# Hammerhead_-_MAX11300_Analog_Hub_R1_1.net
KiCad netlist of a schematic drawn in Altium Designer
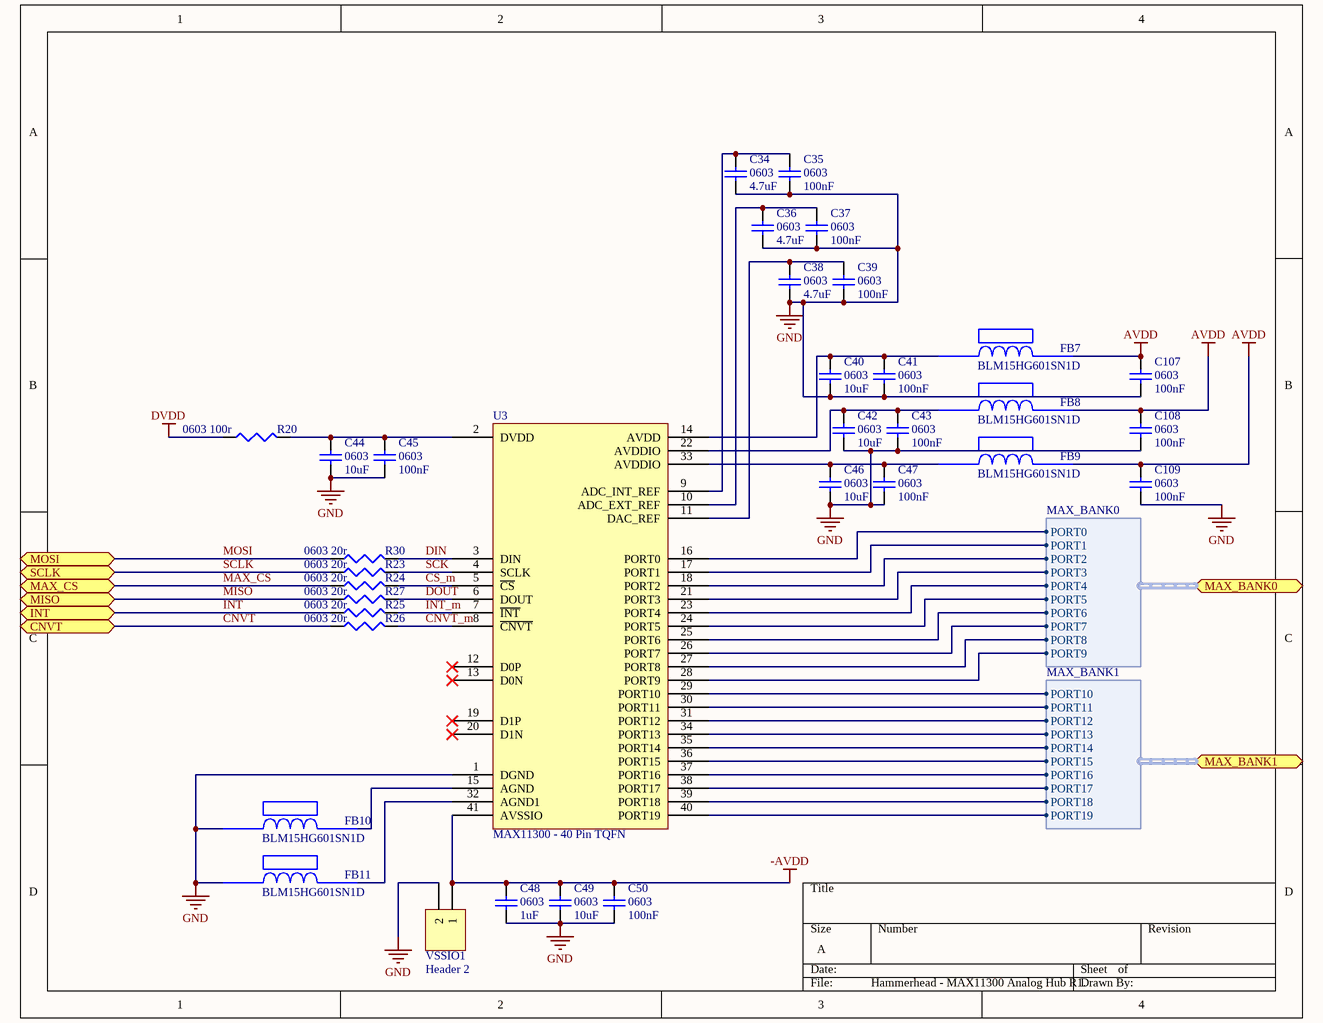
[diagram p0: Hammerhead - MAX11300 Analog Hub R1.1.SchDoc]

(export (version "E")
  (design (tool "Eeschema 10.0.6"))
  (components
    (comp (ref "C34")
      (value "0603")
      (footprint "1608[0603]")
      (description "Capacitor (Semiconductor SIM Model)")
      (fields (field (name "ALTIUM_VALUE") "4.7uF") (field (name "PUBLISHER") "Altium Limited"))
      (libsource (lib "Miscellaneous Devices") (part "Cap Semi"))
    )
    (comp (ref "C35")
      (value "0603")
      (footprint "1608[0603]")
      (description "Capacitor (Semiconductor SIM Model)")
      (fields (field (name "ALTIUM_VALUE") "100nF") (field (name "PUBLISHER") "Altium Limited"))
      (libsource (lib "Miscellaneous Devices") (part "Cap Semi"))
    )
    (comp (ref "C36")
      (value "0603")
      (footprint "1608[0603]")
      (description "Capacitor (Semiconductor SIM Model)")
      (fields (field (name "ALTIUM_VALUE") "4.7uF") (field (name "PUBLISHER") "Altium Limited"))
      (libsource (lib "Miscellaneous Devices") (part "Cap Semi"))
    )
    (comp (ref "C37")
      (value "0603")
      (footprint "1608[0603]")
      (description "Capacitor (Semiconductor SIM Model)")
      (fields (field (name "ALTIUM_VALUE") "100nF") (field (name "PUBLISHER") "Altium Limited"))
      (libsource (lib "Miscellaneous Devices") (part "Cap Semi"))
    )
    (comp (ref "C38")
      (value "0603")
      (footprint "1608[0603]")
      (description "Capacitor (Semiconductor SIM Model)")
      (fields (field (name "ALTIUM_VALUE") "4.7uF") (field (name "PUBLISHER") "Altium Limited"))
      (libsource (lib "Miscellaneous Devices") (part "Cap Semi"))
    )
    (comp (ref "C39")
      (value "0603")
      (footprint "1608[0603]")
      (description "Capacitor (Semiconductor SIM Model)")
      (fields (field (name "ALTIUM_VALUE") "100nF") (field (name "PUBLISHER") "Altium Limited"))
      (libsource (lib "Miscellaneous Devices") (part "Cap Semi"))
    )
    (comp (ref "C40")
      (value "0603")
      (footprint "1608[0603]")
      (description "Capacitor (Semiconductor SIM Model)")
      (fields (field (name "ALTIUM_VALUE") "10uF") (field (name "PUBLISHER") "Altium Limited"))
      (libsource (lib "Miscellaneous Devices") (part "Cap Semi"))
    )
    (comp (ref "C41")
      (value "0603")
      (footprint "1608[0603]")
      (description "Capacitor (Semiconductor SIM Model)")
      (fields (field (name "ALTIUM_VALUE") "100nF") (field (name "PUBLISHER") "Altium Limited"))
      (libsource (lib "Miscellaneous Devices") (part "Cap Semi"))
    )
    (comp (ref "C42")
      (value "0603")
      (footprint "1608[0603]")
      (description "Capacitor (Semiconductor SIM Model)")
      (fields (field (name "ALTIUM_VALUE") "10uF") (field (name "PUBLISHER") "Altium Limited"))
      (libsource (lib "Miscellaneous Devices") (part "Cap Semi"))
    )
    (comp (ref "C43")
      (value "0603")
      (footprint "1608[0603]")
      (description "Capacitor (Semiconductor SIM Model)")
      (fields (field (name "ALTIUM_VALUE") "100nF") (field (name "PUBLISHER") "Altium Limited"))
      (libsource (lib "Miscellaneous Devices") (part "Cap Semi"))
    )
    (comp (ref "C44")
      (value "0603")
      (footprint "1608[0603]")
      (description "Capacitor (Semiconductor SIM Model)")
      (fields (field (name "ALTIUM_VALUE") "10uF") (field (name "PUBLISHER") "Altium Limited"))
      (libsource (lib "Miscellaneous Devices") (part "Cap Semi"))
    )
    (comp (ref "C45")
      (value "0603")
      (footprint "1608[0603]")
      (description "Capacitor (Semiconductor SIM Model)")
      (fields (field (name "ALTIUM_VALUE") "100nF") (field (name "PUBLISHER") "Altium Limited"))
      (libsource (lib "Miscellaneous Devices") (part "Cap Semi"))
    )
    (comp (ref "C46")
      (value "0603")
      (footprint "1608[0603]")
      (description "Capacitor (Semiconductor SIM Model)")
      (fields (field (name "ALTIUM_VALUE") "10uF") (field (name "PUBLISHER") "Altium Limited"))
      (libsource (lib "Miscellaneous Devices") (part "Cap Semi"))
    )
    (comp (ref "C47")
      (value "0603")
      (footprint "1608[0603]")
      (description "Capacitor (Semiconductor SIM Model)")
      (fields (field (name "ALTIUM_VALUE") "100nF") (field (name "PUBLISHER") "Altium Limited"))
      (libsource (lib "Miscellaneous Devices") (part "Cap Semi"))
    )
    (comp (ref "C48")
      (value "0603")
      (footprint "1608[0603]")
      (description "Capacitor (Semiconductor SIM Model)")
      (fields (field (name "ALTIUM_VALUE") "1uF") (field (name "PUBLISHER") "Altium Limited"))
      (libsource (lib "Miscellaneous Devices") (part "Cap Semi"))
    )
    (comp (ref "C49")
      (value "0603")
      (footprint "1608[0603]")
      (description "Capacitor (Semiconductor SIM Model)")
      (fields (field (name "ALTIUM_VALUE") "10uF") (field (name "PUBLISHER") "Altium Limited"))
      (libsource (lib "Miscellaneous Devices") (part "Cap Semi"))
    )
    (comp (ref "C50")
      (value "0603")
      (footprint "1608[0603]")
      (description "Capacitor (Semiconductor SIM Model)")
      (fields (field (name "ALTIUM_VALUE") "100nF") (field (name "PUBLISHER") "Altium Limited"))
      (libsource (lib "Miscellaneous Devices") (part "Cap Semi"))
    )
    (comp (ref "C107")
      (value "0603")
      (footprint "1608[0603]")
      (description "Capacitor (Semiconductor SIM Model)")
      (fields (field (name "ALTIUM_VALUE") "100nF") (field (name "PUBLISHER") "Altium Limited"))
      (libsource (lib "Miscellaneous Devices") (part "Cap Semi"))
    )
    (comp (ref "C108")
      (value "0603")
      (footprint "1608[0603]")
      (description "Capacitor (Semiconductor SIM Model)")
      (fields (field (name "ALTIUM_VALUE") "100nF") (field (name "PUBLISHER") "Altium Limited"))
      (libsource (lib "Miscellaneous Devices") (part "Cap Semi"))
    )
    (comp (ref "C109")
      (value "0603")
      (footprint "1608[0603]")
      (description "Capacitor (Semiconductor SIM Model)")
      (fields (field (name "ALTIUM_VALUE") "100nF") (field (name "PUBLISHER") "Altium Limited"))
      (libsource (lib "Miscellaneous Devices") (part "Cap Semi"))
    )
    (comp (ref "FB7")
      (value "BLM15HG601SN1D")
      (footprint "BLM18PG121SN1D")
      (libsource (lib "AHD Part Library") (part "BLM15HG601SN1D"))
    )
    (comp (ref "FB8")
      (value "BLM15HG601SN1D")
      (footprint "BLM18PG121SN1D")
      (libsource (lib "AHD Part Library") (part "BLM15HG601SN1D"))
    )
    (comp (ref "FB9")
      (value "BLM15HG601SN1D")
      (footprint "BLM18PG121SN1D")
      (libsource (lib "AHD Part Library") (part "BLM15HG601SN1D"))
    )
    (comp (ref "FB10")
      (value "BLM15HG601SN1D")
      (footprint "BLM18PG121SN1D")
      (libsource (lib "AHD Part Library") (part "BLM15HG601SN1D"))
    )
    (comp (ref "FB11")
      (value "BLM15HG601SN1D")
      (footprint "BLM18PG121SN1D")
      (libsource (lib "AHD Part Library") (part "BLM15HG601SN1D"))
    )
    (comp (ref "R20")
      (value "0603")
      (footprint "J1-0603")
      (description "Resistor")
      (fields (field (name "ALTIUM_VALUE") "100r") (field (name "PUBLISHER") "Altium Limited"))
      (libsource (lib "Miscellaneous Devices") (part "Res3"))
    )
    (comp (ref "R23")
      (value "0603")
      (footprint "J1-0603")
      (description "Resistor")
      (fields (field (name "ALTIUM_VALUE") "20r") (field (name "PUBLISHER") "Altium Limited"))
      (libsource (lib "Miscellaneous Devices") (part "Res3"))
    )
    (comp (ref "R24")
      (value "0603")
      (footprint "J1-0603")
      (description "Resistor")
      (fields (field (name "ALTIUM_VALUE") "20r") (field (name "PUBLISHER") "Altium Limited"))
      (libsource (lib "Miscellaneous Devices") (part "Res3"))
    )
    (comp (ref "R25")
      (value "0603")
      (footprint "J1-0603")
      (description "Resistor")
      (fields (field (name "ALTIUM_VALUE") "20r") (field (name "PUBLISHER") "Altium Limited"))
      (libsource (lib "Miscellaneous Devices") (part "Res3"))
    )
    (comp (ref "R26")
      (value "0603")
      (footprint "J1-0603")
      (description "Resistor")
      (fields (field (name "ALTIUM_VALUE") "20r") (field (name "PUBLISHER") "Altium Limited"))
      (libsource (lib "Miscellaneous Devices") (part "Res3"))
    )
    (comp (ref "R27")
      (value "0603")
      (footprint "J1-0603")
      (description "Resistor")
      (fields (field (name "ALTIUM_VALUE") "20r") (field (name "PUBLISHER") "Altium Limited"))
      (libsource (lib "Miscellaneous Devices") (part "Res3"))
    )
    (comp (ref "R30")
      (value "0603")
      (footprint "J1-0603")
      (description "Resistor")
      (fields (field (name "ALTIUM_VALUE") "20r") (field (name "PUBLISHER") "Altium Limited"))
      (libsource (lib "Miscellaneous Devices") (part "Res3"))
    )
    (comp (ref "U3")
      (value "MAX11300 - 40 Pin TQFN")
      (footprint "Maxim T4066+3 40 pin TQFN")
      (description "MAX11300")
      (libsource (lib "SunIO Schematic Symbol Lib") (part "MAX11300 - 40 Pin TQFN"))
    )
    (comp (ref "VSSIO1")
      (value "Header 2")
      (footprint "HDR1X2")
      (description "Header, 2-Pin")
      (fields (field (name "PUBLISHER") "Altium Limited"))
      (libsource (lib "Miscellaneous Connectors") (part "Header 2"))
    )
  )
  (nets
    (net (code "3") (name "-AVDD") (class "Default")
      (node (ref "C48") (pin "2") (pinfunction "2_2") (pintype "passive"))
      (node (ref "C49") (pin "2") (pinfunction "2_2") (pintype "passive"))
      (node (ref "C50") (pin "2") (pinfunction "2_2") (pintype "passive"))
      (node (ref "U3") (pin "41") (pinfunction "AVSSIO_41") (pintype "passive"))
      (node (ref "VSSIO1") (pin "1") (pinfunction "1_1") (pintype "passive"))
    )
    (net (code "4") (name "/CNVT") (class "Default")
      (node (ref "R26") (pin "1") (pinfunction "1_1") (pintype "passive"))
    )
    (net (code "5") (name "/CNVT_m") (class "Default")
      (node (ref "R26") (pin "2") (pinfunction "2_2") (pintype "passive"))
      (node (ref "U3") (pin "8") (pinfunction "~{CNVT}_8") (pintype "passive"))
    )
    (net (code "6") (name "/CS_m") (class "Default")
      (node (ref "R24") (pin "2") (pinfunction "2_2") (pintype "passive"))
      (node (ref "U3") (pin "5") (pinfunction "~{CS}_5") (pintype "passive"))
    )
    (net (code "7") (name "/DIN") (class "Default")
      (node (ref "R30") (pin "2") (pinfunction "2_2") (pintype "passive"))
      (node (ref "U3") (pin "3") (pinfunction "DIN_3") (pintype "passive"))
    )
    (net (code "8") (name "/DOUT") (class "Default")
      (node (ref "R27") (pin "2") (pinfunction "2_2") (pintype "passive"))
      (node (ref "U3") (pin "6") (pinfunction "DOUT_6") (pintype "passive"))
    )
    (net (code "9") (name "/INT") (class "Default")
      (node (ref "R25") (pin "1") (pinfunction "1_1") (pintype "passive"))
    )
    (net (code "10") (name "/INT_m") (class "Default")
      (node (ref "R25") (pin "2") (pinfunction "2_2") (pintype "passive"))
      (node (ref "U3") (pin "7") (pinfunction "~{INT}_7") (pintype "passive"))
    )
    (net (code "11") (name "/MAX_CS") (class "Default")
      (node (ref "R24") (pin "1") (pinfunction "1_1") (pintype "passive"))
    )
    (net (code "12") (name "/MISO") (class "Default")
      (node (ref "R27") (pin "1") (pinfunction "1_1") (pintype "passive"))
    )
    (net (code "13") (name "/MOSI") (class "Default")
      (node (ref "R30") (pin "1") (pinfunction "1_1") (pintype "passive"))
    )
    (net (code "14") (name "/PORT0") (class "Default")
      (node (ref "U3") (pin "16") (pinfunction "PORT0_16") (pintype "passive"))
    )
    (net (code "15") (name "/PORT1") (class "Default")
      (node (ref "U3") (pin "17") (pinfunction "PORT1_17") (pintype "passive"))
    )
    (net (code "16") (name "/PORT2") (class "Default")
      (node (ref "U3") (pin "18") (pinfunction "PORT2_18") (pintype "passive"))
    )
    (net (code "17") (name "/PORT3") (class "Default")
      (node (ref "U3") (pin "21") (pinfunction "PORT3_21") (pintype "passive"))
    )
    (net (code "18") (name "/PORT4") (class "Default")
      (node (ref "U3") (pin "23") (pinfunction "PORT4_23") (pintype "passive"))
    )
    (net (code "19") (name "/PORT5") (class "Default")
      (node (ref "U3") (pin "24") (pinfunction "PORT5_24") (pintype "passive"))
    )
    (net (code "20") (name "/PORT6") (class "Default")
      (node (ref "U3") (pin "25") (pinfunction "PORT6_25") (pintype "passive"))
    )
    (net (code "21") (name "/PORT7") (class "Default")
      (node (ref "U3") (pin "26") (pinfunction "PORT7_26") (pintype "passive"))
    )
    (net (code "22") (name "/PORT8") (class "Default")
      (node (ref "U3") (pin "27") (pinfunction "PORT8_27") (pintype "passive"))
    )
    (net (code "23") (name "/PORT9") (class "Default")
      (node (ref "U3") (pin "28") (pinfunction "PORT9_28") (pintype "passive"))
    )
    (net (code "24") (name "/PORT10") (class "Default")
      (node (ref "U3") (pin "29") (pinfunction "PORT10_29") (pintype "passive"))
    )
    (net (code "25") (name "/PORT11") (class "Default")
      (node (ref "U3") (pin "30") (pinfunction "PORT11_30") (pintype "passive"))
    )
    (net (code "26") (name "/PORT12") (class "Default")
      (node (ref "U3") (pin "31") (pinfunction "PORT12_31") (pintype "passive"))
    )
    (net (code "27") (name "/PORT13") (class "Default")
      (node (ref "U3") (pin "34") (pinfunction "PORT13_34") (pintype "passive"))
    )
    (net (code "28") (name "/PORT14") (class "Default")
      (node (ref "U3") (pin "35") (pinfunction "PORT14_35") (pintype "passive"))
    )
    (net (code "29") (name "/PORT15") (class "Default")
      (node (ref "U3") (pin "36") (pinfunction "PORT15_36") (pintype "passive"))
    )
    (net (code "30") (name "/PORT16") (class "Default")
      (node (ref "U3") (pin "37") (pinfunction "PORT16_37") (pintype "passive"))
    )
    (net (code "31") (name "/PORT17") (class "Default")
      (node (ref "U3") (pin "38") (pinfunction "PORT17_38") (pintype "passive"))
    )
    (net (code "32") (name "/PORT18") (class "Default")
      (node (ref "U3") (pin "39") (pinfunction "PORT18_39") (pintype "passive"))
    )
    (net (code "33") (name "/PORT19") (class "Default")
      (node (ref "U3") (pin "40") (pinfunction "PORT19_40") (pintype "passive"))
    )
    (net (code "34") (name "/SCK") (class "Default")
      (node (ref "R23") (pin "2") (pinfunction "2_2") (pintype "passive"))
      (node (ref "U3") (pin "4") (pinfunction "SCLK_4") (pintype "passive"))
    )
    (net (code "35") (name "/SCLK") (class "Default")
      (node (ref "R23") (pin "1") (pinfunction "1_1") (pintype "passive"))
    )
    (net (code "38") (name "AVDD") (class "Default")
      (node (ref "C107") (pin "2") (pinfunction "2_2") (pintype "passive"))
      (node (ref "C108") (pin "2") (pinfunction "2_2") (pintype "passive"))
      (node (ref "C109") (pin "2") (pinfunction "2_2") (pintype "passive"))
      (node (ref "FB7") (pin "2") (pinfunction "2_2") (pintype "passive"))
      (node (ref "FB8") (pin "2") (pinfunction "2_2") (pintype "passive"))
      (node (ref "FB9") (pin "2") (pinfunction "2_2") (pintype "passive"))
    )
    (net (code "39") (name "DVDD") (class "Default")
      (node (ref "R20") (pin "1") (pinfunction "1_1") (pintype "passive"))
    )
    (net (code "40") (name "GND") (class "Default")
      (node (ref "C107") (pin "1") (pinfunction "1_1") (pintype "passive"))
      (node (ref "C108") (pin "1") (pinfunction "1_1") (pintype "passive"))
      (node (ref "C109") (pin "1") (pinfunction "1_1") (pintype "passive"))
      (node (ref "C34") (pin "1") (pinfunction "1_1") (pintype "passive"))
      (node (ref "C35") (pin "1") (pinfunction "1_1") (pintype "passive"))
      (node (ref "C36") (pin "1") (pinfunction "1_1") (pintype "passive"))
      (node (ref "C37") (pin "1") (pinfunction "1_1") (pintype "passive"))
      (node (ref "C38") (pin "1") (pinfunction "1_1") (pintype "passive"))
      (node (ref "C39") (pin "1") (pinfunction "1_1") (pintype "passive"))
      (node (ref "C40") (pin "1") (pinfunction "1_1") (pintype "passive"))
      (node (ref "C41") (pin "1") (pinfunction "1_1") (pintype "passive"))
      (node (ref "C42") (pin "1") (pinfunction "1_1") (pintype "passive"))
      (node (ref "C43") (pin "1") (pinfunction "1_1") (pintype "passive"))
      (node (ref "C44") (pin "1") (pinfunction "1_1") (pintype "passive"))
      (node (ref "C45") (pin "1") (pinfunction "1_1") (pintype "passive"))
      (node (ref "C46") (pin "1") (pinfunction "1_1") (pintype "passive"))
      (node (ref "C47") (pin "1") (pinfunction "1_1") (pintype "passive"))
      (node (ref "C48") (pin "1") (pinfunction "1_1") (pintype "passive"))
      (node (ref "C49") (pin "1") (pinfunction "1_1") (pintype "passive"))
      (node (ref "C50") (pin "1") (pinfunction "1_1") (pintype "passive"))
      (node (ref "FB10") (pin "1") (pinfunction "1_1") (pintype "passive"))
      (node (ref "FB11") (pin "1") (pinfunction "1_1") (pintype "passive"))
      (node (ref "U3") (pin "1") (pinfunction "DGND_1") (pintype "passive"))
      (node (ref "VSSIO1") (pin "2") (pinfunction "2_2") (pintype "passive"))
    )
    (net (code "41") (name "Net-(C42-Pad2)") (class "Default")
      (node (ref "C42") (pin "2") (pinfunction "2_2") (pintype "passive"))
      (node (ref "C43") (pin "2") (pinfunction "2_2") (pintype "passive"))
      (node (ref "FB8") (pin "1") (pinfunction "1_1") (pintype "passive"))
      (node (ref "U3") (pin "22") (pinfunction "AVDDIO_22") (pintype "passive"))
    )
    (net (code "42") (name "Net-(C46-Pad2)") (class "Default")
      (node (ref "C46") (pin "2") (pinfunction "2_2") (pintype "passive"))
      (node (ref "C47") (pin "2") (pinfunction "2_2") (pintype "passive"))
      (node (ref "FB9") (pin "1") (pinfunction "1_1") (pintype "passive"))
      (node (ref "U3") (pin "33") (pinfunction "AVDDIO_33") (pintype "passive"))
    )
    (net (code "43") (name "Net-(U3-ADC_EXT_REF)") (class "Default")
      (node (ref "C36") (pin "2") (pinfunction "2_2") (pintype "passive"))
      (node (ref "C37") (pin "2") (pinfunction "2_2") (pintype "passive"))
      (node (ref "U3") (pin "10") (pinfunction "ADC_EXT_REF_10") (pintype "passive"))
    )
    (net (code "44") (name "Net-(U3-ADC_INT_REF)") (class "Default")
      (node (ref "C34") (pin "2") (pinfunction "2_2") (pintype "passive"))
      (node (ref "C35") (pin "2") (pinfunction "2_2") (pintype "passive"))
      (node (ref "U3") (pin "9") (pinfunction "ADC_INT_REF_9") (pintype "passive"))
    )
    (net (code "45") (name "Net-(U3-AGND)") (class "Default")
      (node (ref "FB10") (pin "2") (pinfunction "2_2") (pintype "passive"))
      (node (ref "U3") (pin "15") (pinfunction "AGND_15") (pintype "passive"))
    )
    (net (code "46") (name "Net-(U3-AGND1)") (class "Default")
      (node (ref "FB11") (pin "2") (pinfunction "2_2") (pintype "passive"))
      (node (ref "U3") (pin "32") (pinfunction "AGND1_32") (pintype "passive"))
    )
    (net (code "47") (name "Net-(U3-AVDD)") (class "Default")
      (node (ref "C40") (pin "2") (pinfunction "2_2") (pintype "passive"))
      (node (ref "C41") (pin "2") (pinfunction "2_2") (pintype "passive"))
      (node (ref "FB7") (pin "1") (pinfunction "1_1") (pintype "passive"))
      (node (ref "U3") (pin "14") (pinfunction "AVDD_14") (pintype "passive"))
    )
    (net (code "48") (name "Net-(U3-DAC_REF)") (class "Default")
      (node (ref "C38") (pin "2") (pinfunction "2_2") (pintype "passive"))
      (node (ref "C39") (pin "2") (pinfunction "2_2") (pintype "passive"))
      (node (ref "U3") (pin "11") (pinfunction "DAC_REF_11") (pintype "passive"))
    )
    (net (code "49") (name "Net-(U3-DVDD)") (class "Default")
      (node (ref "C44") (pin "2") (pinfunction "2_2") (pintype "passive"))
      (node (ref "C45") (pin "2") (pinfunction "2_2") (pintype "passive"))
      (node (ref "R20") (pin "2") (pinfunction "2_2") (pintype "passive"))
      (node (ref "U3") (pin "2") (pinfunction "DVDD_2") (pintype "passive"))
    )
    (net (code "50") (name "unconnected-(U3-D0N-Pad13)") (class "Default")
      (node (ref "U3") (pin "13") (pinfunction "D0N_13") (pintype "passive+no_connect"))
    )
    (net (code "51") (name "unconnected-(U3-D0P-Pad12)") (class "Default")
      (node (ref "U3") (pin "12") (pinfunction "D0P_12") (pintype "passive+no_connect"))
    )
    (net (code "52") (name "unconnected-(U3-D1N-Pad20)") (class "Default")
      (node (ref "U3") (pin "20") (pinfunction "D1N_20") (pintype "passive+no_connect"))
    )
    (net (code "53") (name "unconnected-(U3-D1P-Pad19)") (class "Default")
      (node (ref "U3") (pin "19") (pinfunction "D1P_19") (pintype "passive+no_connect"))
    )
  )
)
